# VIM2-AccelController.net
KiCad netlist of a schematic drawn in EAGLE
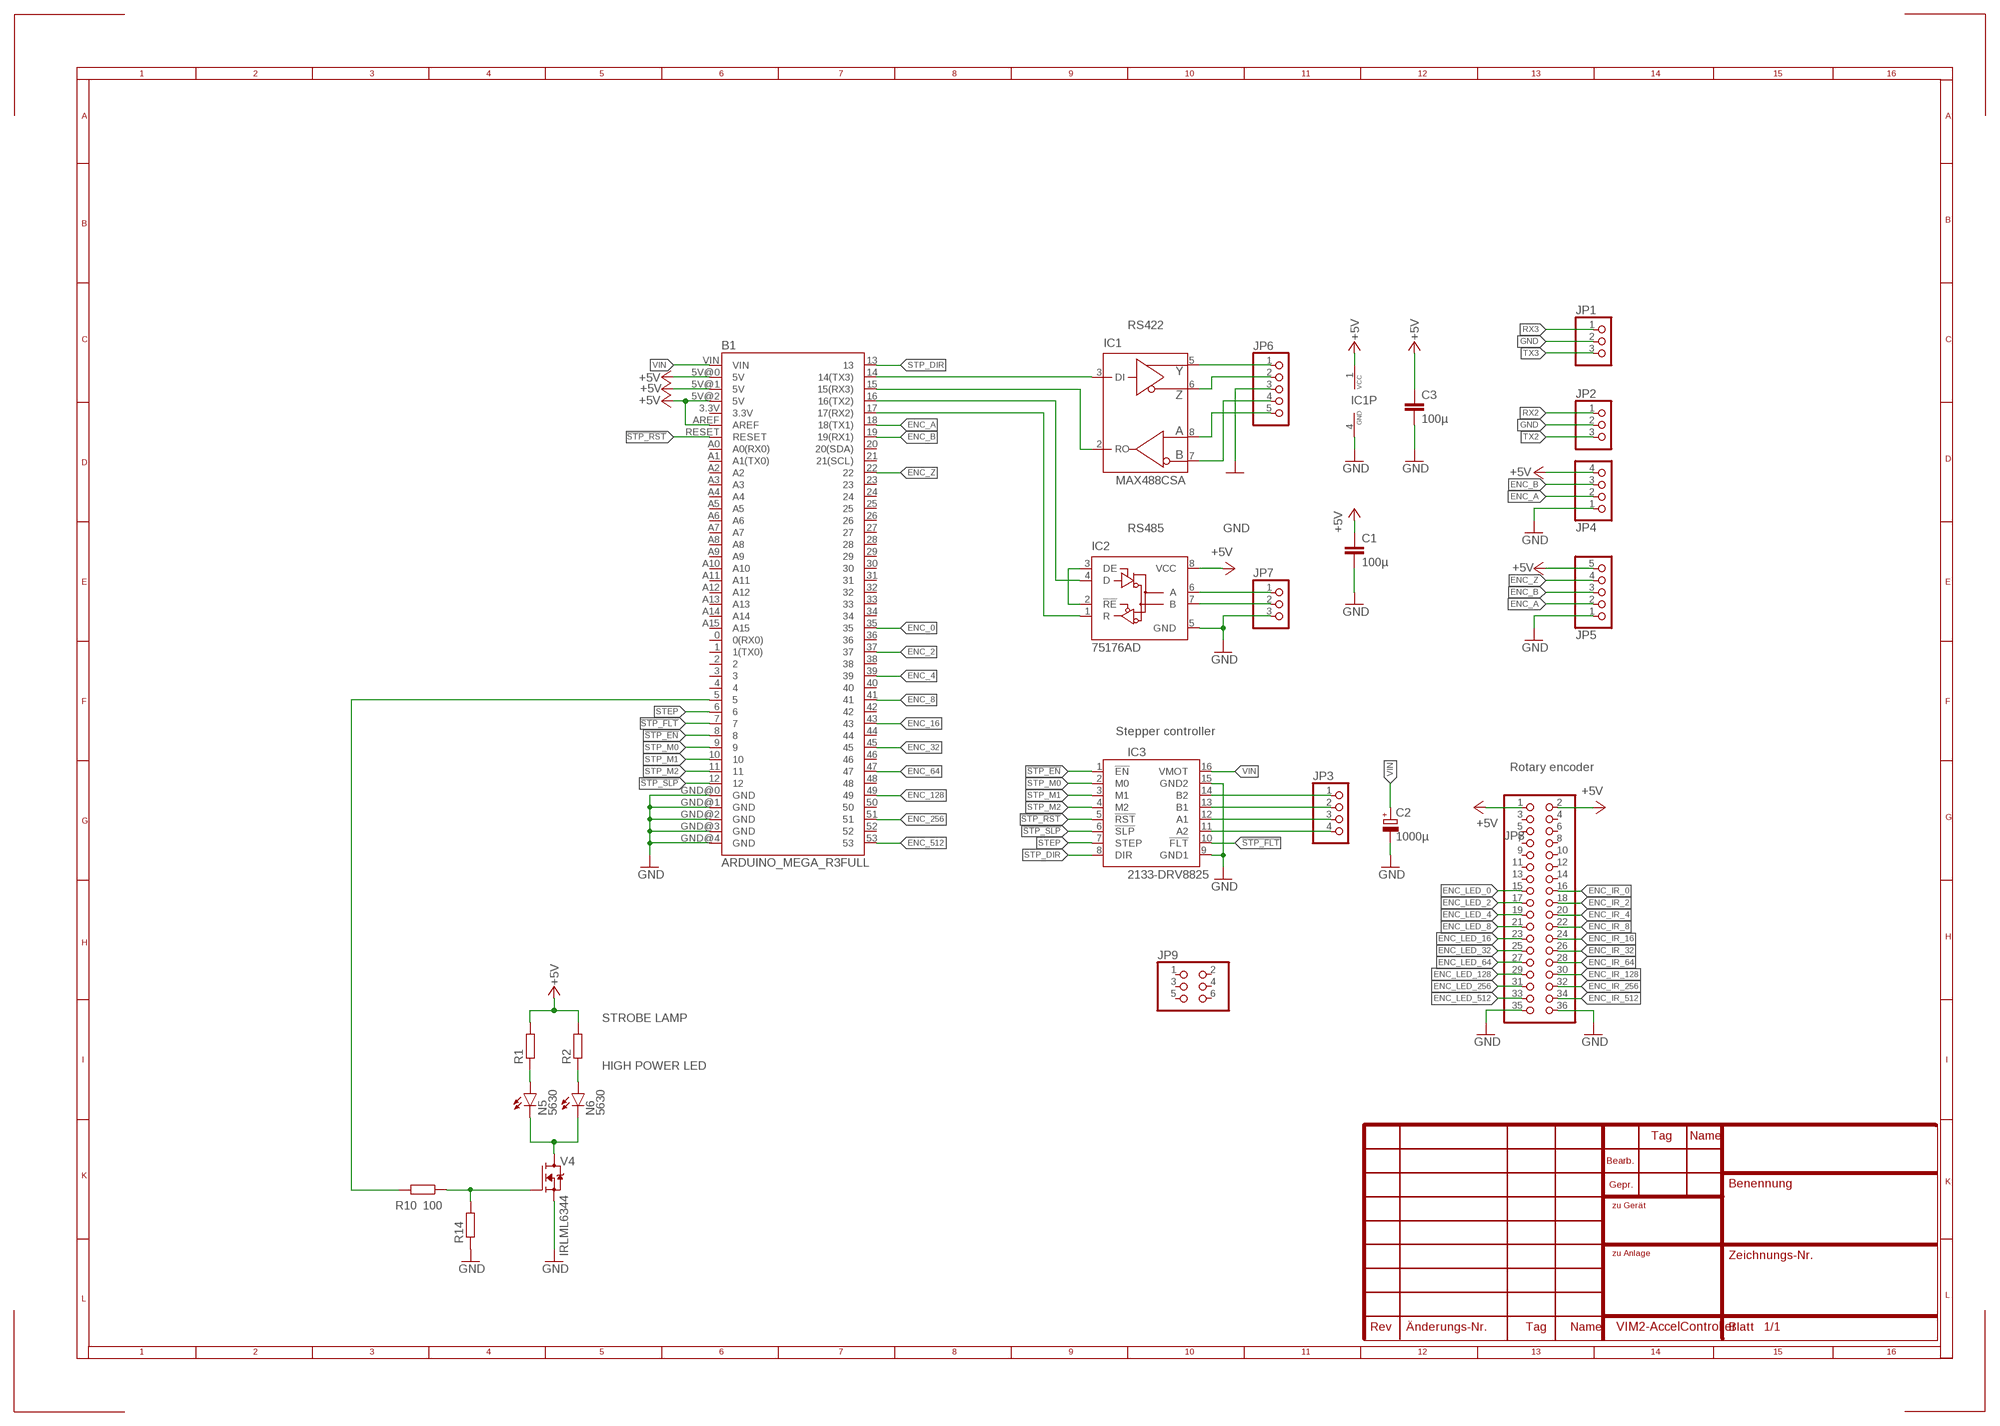
[diagram p0: schematic, sheet 1]

(export (version "E")
  (design (tool "Eeschema 10.0.6"))
  (components
    (comp (ref "B1")
      (value "ARDUINO_MEGA_R3FULL")
      (footprint "eagle-import:ARDUINO_MEGA")
      (libsource (lib "eagle-import") (part "ARDUINO_MEGA_R3FULL"))
    )
    (comp (ref "C1")
      (value "100µ")
      (footprint "eagle-import:C0805K")
      (libsource (lib "eagle-import") (part "C-EUC0805K"))
    )
    (comp (ref "C2")
      (value "1000µ")
      (footprint "eagle-import:E5-8,5")
      (libsource (lib "eagle-import") (part "CPOL-EUE5-8.5"))
    )
    (comp (ref "C3")
      (value "100µ")
      (footprint "eagle-import:C0805K")
      (libsource (lib "eagle-import") (part "C-EUC0805K"))
    )
    (comp (ref "IC1")
      (value "MAX488CSA")
      (footprint "eagle-import:SO08")
      (fields (field (name "MF") "MAXIM"))
      (libsource (lib "eagle-import") (part "MAX488CSA"))
    )
    (comp (ref "IC2")
      (value "75176AD")
      (footprint "eagle-import:D_R-PDSO-G8")
      (libsource (lib "eagle-import") (part "75176AD"))
    )
    (comp (ref "IC3")
      (value "2133-DRV8825")
      (footprint "eagle-import:DRV8825")
      (libsource (lib "eagle-import") (part "2133-DRV8825"))
    )
    (comp (ref "JP1")
      (value "PINHD-1X3")
      (footprint "eagle-import:1X03")
      (libsource (lib "eagle-import") (part "PINHD-1X3"))
    )
    (comp (ref "JP2")
      (value "PINHD-1X3")
      (footprint "eagle-import:1X03")
      (libsource (lib "eagle-import") (part "PINHD-1X3"))
    )
    (comp (ref "JP3")
      (value "PINHD-1X4/90")
      (footprint "eagle-import:1X04_90")
      (libsource (lib "eagle-import") (part "PINHD-1X4/90"))
    )
    (comp (ref "JP4")
      (value "PINHD-1X4")
      (footprint "eagle-import:1X04")
      (libsource (lib "eagle-import") (part "PINHD-1X4"))
    )
    (comp (ref "JP5")
      (value "PINHD-1X5")
      (footprint "eagle-import:1X05")
      (libsource (lib "eagle-import") (part "PINHD-1X5"))
    )
    (comp (ref "JP6")
      (value "PINHD-1X5")
      (footprint "eagle-import:1X05")
      (libsource (lib "eagle-import") (part "PINHD-1X5"))
    )
    (comp (ref "JP7")
      (value "PINHD-1X3")
      (footprint "eagle-import:1X03")
      (libsource (lib "eagle-import") (part "PINHD-1X3"))
    )
    (comp (ref "JP8")
      (value "PINHD-2X18")
      (footprint "eagle-import:2X18")
      (libsource (lib "eagle-import") (part "PINHD-2X18"))
    )
    (comp (ref "JP9")
      (value "PINHD-2X3")
      (footprint "eagle-import:2X03")
      (libsource (lib "eagle-import") (part "PINHD-2X3"))
    )
    (comp (ref "N5")
      (value "5630")
      (footprint "eagle-import:5730")
      (libsource (lib "eagle-import") (part "5630"))
    )
    (comp (ref "N6")
      (value "5630")
      (footprint "eagle-import:5730")
      (libsource (lib "eagle-import") (part "5630"))
    )
    (comp (ref "R1")
      (value "100")
      (footprint "eagle-import:R0805")
      (libsource (lib "eagle-import") (part "R-EU_R0805"))
    )
    (comp (ref "R2")
      (value "100")
      (footprint "eagle-import:R0805")
      (libsource (lib "eagle-import") (part "R-EU_R0805"))
    )
    (comp (ref "R10")
      (value "100")
      (footprint "eagle-import:R0805")
      (libsource (lib "eagle-import") (part "R-EU_R0805"))
    )
    (comp (ref "R14")
      (value "4k7")
      (footprint "eagle-import:R0805")
      (libsource (lib "eagle-import") (part "R-EU_R0805"))
    )
    (comp (ref "V4")
      (value "IRLML6344")
      (footprint "eagle-import:SOT23")
      (libsource (lib "eagle-import") (part "IRLML6344"))
    )
  )
  (nets
    (net (code "1") (name "+5V") (class "Default")
      (node (ref "B1") (pin "5V@0") (pinfunction "5V_5V@0") (pintype "bidirectional"))
      (node (ref "B1") (pin "5V@1") (pinfunction "5V_5V@1") (pintype "bidirectional"))
      (node (ref "B1") (pin "5V@2") (pinfunction "5V_5V@2") (pintype "bidirectional"))
      (node (ref "B1") (pin "AREF") (pinfunction "AREF_AREF") (pintype "bidirectional"))
      (node (ref "C1") (pin "1") (pinfunction "1_1") (pintype "passive"))
      (node (ref "C3") (pin "1") (pinfunction "1_1") (pintype "passive"))
      (node (ref "IC1") (pin "1") (pinfunction "VCC_1") (pintype "power_in"))
      (node (ref "IC2") (pin "8") (pinfunction "VCC_8") (pintype "power_in"))
      (node (ref "JP4") (pin "4") (pinfunction "4_4") (pintype "passive"))
      (node (ref "JP5") (pin "5") (pinfunction "5_5") (pintype "passive"))
      (node (ref "JP8") (pin "1") (pinfunction "1_1") (pintype "passive"))
      (node (ref "JP8") (pin "2") (pinfunction "2_2") (pintype "passive"))
      (node (ref "R1") (pin "2") (pinfunction "2_2") (pintype "passive"))
      (node (ref "R2") (pin "2") (pinfunction "2_2") (pintype "passive"))
    )
    (net (code "2") (name "/~{STP_EN}") (class "Default")
      (node (ref "B1") (pin "8") (pinfunction "8_8") (pintype "bidirectional"))
      (node (ref "IC3") (pin "1") (pinfunction "~{EN}_1") (pintype "passive"))
    )
    (net (code "3") (name "/~{STP_FLT}") (class "Default")
      (node (ref "B1") (pin "7") (pinfunction "7_7") (pintype "bidirectional"))
      (node (ref "IC3") (pin "10") (pinfunction "~{FLT}_10") (pintype "open_collector"))
    )
    (net (code "4") (name "/~{STP_RST}") (class "Default")
      (node (ref "B1") (pin "RESET") (pinfunction "RESET_RESET") (pintype "bidirectional"))
      (node (ref "IC3") (pin "5") (pinfunction "~{RST}_5") (pintype "input"))
    )
    (net (code "5") (name "/~{STP_SLP}") (class "Default")
      (node (ref "B1") (pin "12") (pinfunction "12_12") (pintype "bidirectional"))
      (node (ref "IC3") (pin "6") (pinfunction "~{SLP}_6") (pintype "input"))
    )
    (net (code "6") (name "ENC_0") (class "Default")
      (node (ref "B1") (pin "35") (pinfunction "35_35") (pintype "bidirectional"))
    )
    (net (code "7") (name "ENC_2") (class "Default")
      (node (ref "B1") (pin "37") (pinfunction "37_37") (pintype "bidirectional"))
    )
    (net (code "8") (name "ENC_4") (class "Default")
      (node (ref "B1") (pin "39") (pinfunction "39_39") (pintype "bidirectional"))
    )
    (net (code "9") (name "ENC_8") (class "Default")
      (node (ref "B1") (pin "41") (pinfunction "41_41") (pintype "bidirectional"))
    )
    (net (code "10") (name "ENC_16") (class "Default")
      (node (ref "B1") (pin "43") (pinfunction "43_43") (pintype "bidirectional"))
    )
    (net (code "11") (name "ENC_32") (class "Default")
      (node (ref "B1") (pin "45") (pinfunction "45_45") (pintype "bidirectional"))
    )
    (net (code "12") (name "ENC_64") (class "Default")
      (node (ref "B1") (pin "47") (pinfunction "47_47") (pintype "bidirectional"))
    )
    (net (code "13") (name "ENC_128") (class "Default")
      (node (ref "B1") (pin "49") (pinfunction "49_49") (pintype "bidirectional"))
    )
    (net (code "14") (name "ENC_256") (class "Default")
      (node (ref "B1") (pin "51") (pinfunction "51_51") (pintype "bidirectional"))
    )
    (net (code "15") (name "ENC_512") (class "Default")
      (node (ref "B1") (pin "53") (pinfunction "53_53") (pintype "bidirectional"))
    )
    (net (code "16") (name "ENC_A") (class "Default")
      (node (ref "B1") (pin "18") (pinfunction "18(TX1)_18") (pintype "bidirectional"))
      (node (ref "JP4") (pin "2") (pinfunction "2_2") (pintype "passive"))
      (node (ref "JP5") (pin "2") (pinfunction "2_2") (pintype "passive"))
    )
    (net (code "17") (name "ENC_B") (class "Default")
      (node (ref "B1") (pin "19") (pinfunction "19(RX1)_19") (pintype "bidirectional"))
      (node (ref "JP4") (pin "3") (pinfunction "3_3") (pintype "passive"))
      (node (ref "JP5") (pin "3") (pinfunction "3_3") (pintype "passive"))
    )
    (net (code "18") (name "ENC_IR_0") (class "Default")
      (node (ref "JP8") (pin "16") (pinfunction "16_16") (pintype "passive"))
    )
    (net (code "19") (name "ENC_IR_2") (class "Default")
      (node (ref "JP8") (pin "18") (pinfunction "18_18") (pintype "passive"))
    )
    (net (code "20") (name "ENC_IR_4") (class "Default")
      (node (ref "JP8") (pin "20") (pinfunction "20_20") (pintype "passive"))
    )
    (net (code "21") (name "ENC_IR_8") (class "Default")
      (node (ref "JP8") (pin "22") (pinfunction "22_22") (pintype "passive"))
    )
    (net (code "22") (name "ENC_IR_16") (class "Default")
      (node (ref "JP8") (pin "24") (pinfunction "24_24") (pintype "passive"))
    )
    (net (code "23") (name "ENC_IR_32") (class "Default")
      (node (ref "JP8") (pin "26") (pinfunction "26_26") (pintype "passive"))
    )
    (net (code "24") (name "ENC_IR_64") (class "Default")
      (node (ref "JP8") (pin "28") (pinfunction "28_28") (pintype "passive"))
    )
    (net (code "25") (name "ENC_IR_128") (class "Default")
      (node (ref "JP8") (pin "30") (pinfunction "30_30") (pintype "passive"))
    )
    (net (code "26") (name "ENC_IR_256") (class "Default")
      (node (ref "JP8") (pin "32") (pinfunction "32_32") (pintype "passive"))
    )
    (net (code "27") (name "ENC_IR_512") (class "Default")
      (node (ref "JP8") (pin "34") (pinfunction "34_34") (pintype "passive"))
    )
    (net (code "28") (name "ENC_LED_0") (class "Default")
      (node (ref "JP8") (pin "15") (pinfunction "15_15") (pintype "passive"))
    )
    (net (code "29") (name "ENC_LED_2") (class "Default")
      (node (ref "JP8") (pin "17") (pinfunction "17_17") (pintype "passive"))
    )
    (net (code "30") (name "ENC_LED_4") (class "Default")
      (node (ref "JP8") (pin "19") (pinfunction "19_19") (pintype "passive"))
    )
    (net (code "31") (name "ENC_LED_8") (class "Default")
      (node (ref "JP8") (pin "21") (pinfunction "21_21") (pintype "passive"))
    )
    (net (code "32") (name "ENC_LED_16") (class "Default")
      (node (ref "JP8") (pin "23") (pinfunction "23_23") (pintype "passive"))
    )
    (net (code "33") (name "ENC_LED_32") (class "Default")
      (node (ref "JP8") (pin "25") (pinfunction "25_25") (pintype "passive"))
    )
    (net (code "34") (name "ENC_LED_64") (class "Default")
      (node (ref "JP8") (pin "27") (pinfunction "27_27") (pintype "passive"))
    )
    (net (code "35") (name "ENC_LED_128") (class "Default")
      (node (ref "JP8") (pin "29") (pinfunction "29_29") (pintype "passive"))
    )
    (net (code "36") (name "ENC_LED_256") (class "Default")
      (node (ref "JP8") (pin "31") (pinfunction "31_31") (pintype "passive"))
    )
    (net (code "37") (name "ENC_LED_512") (class "Default")
      (node (ref "JP8") (pin "33") (pinfunction "33_33") (pintype "passive"))
    )
    (net (code "38") (name "ENC_Z") (class "Default")
      (node (ref "B1") (pin "22") (pinfunction "22_22") (pintype "bidirectional"))
      (node (ref "JP5") (pin "4") (pinfunction "4_4") (pintype "passive"))
    )
    (net (code "39") (name "GND") (class "Default")
      (node (ref "B1") (pin "GND@0") (pinfunction "GND_GND@0") (pintype "bidirectional"))
      (node (ref "B1") (pin "GND@1") (pinfunction "GND_GND@1") (pintype "bidirectional"))
      (node (ref "B1") (pin "GND@2") (pinfunction "GND_GND@2") (pintype "bidirectional"))
      (node (ref "B1") (pin "GND@3") (pinfunction "GND_GND@3") (pintype "bidirectional"))
      (node (ref "B1") (pin "GND@4") (pinfunction "GND_GND@4") (pintype "bidirectional"))
      (node (ref "C1") (pin "2") (pinfunction "2_2") (pintype "passive"))
      (node (ref "C2") (pin "-") (pinfunction "-_-") (pintype "passive"))
      (node (ref "C3") (pin "2") (pinfunction "2_2") (pintype "passive"))
      (node (ref "IC1") (pin "4") (pinfunction "GND_4") (pintype "power_in"))
      (node (ref "IC2") (pin "5") (pinfunction "GND_5") (pintype "power_in"))
      (node (ref "IC3") (pin "15") (pinfunction "GND2_15") (pintype "power_in"))
      (node (ref "IC3") (pin "9") (pinfunction "GND1_9") (pintype "power_in"))
      (node (ref "JP1") (pin "2") (pinfunction "2_2") (pintype "passive"))
      (node (ref "JP2") (pin "2") (pinfunction "2_2") (pintype "passive"))
      (node (ref "JP4") (pin "1") (pinfunction "1_1") (pintype "passive"))
      (node (ref "JP5") (pin "1") (pinfunction "1_1") (pintype "passive"))
      (node (ref "JP6") (pin "3") (pinfunction "3_3") (pintype "passive"))
      (node (ref "JP7") (pin "3") (pinfunction "3_3") (pintype "passive"))
      (node (ref "JP8") (pin "35") (pinfunction "35_35") (pintype "passive"))
      (node (ref "JP8") (pin "36") (pinfunction "36_36") (pintype "passive"))
      (node (ref "R14") (pin "1") (pinfunction "1_1") (pintype "passive"))
      (node (ref "V4") (pin "2") (pinfunction "S_2") (pintype "passive"))
    )
    (net (code "40") (name "Net-(B1-Pad5)") (class "Default")
      (node (ref "B1") (pin "5") (pinfunction "5_5") (pintype "bidirectional"))
      (node (ref "R10") (pin "2") (pinfunction "2_2") (pintype "passive"))
    )
    (net (code "41") (name "Net-(IC1A-A)") (class "Default")
      (node (ref "IC1") (pin "8") (pinfunction "A_8") (pintype "input"))
      (node (ref "JP6") (pin "5") (pinfunction "5_5") (pintype "passive"))
    )
    (net (code "42") (name "Net-(IC1A-B)") (class "Default")
      (node (ref "IC1") (pin "7") (pinfunction "B_7") (pintype "input"))
      (node (ref "JP6") (pin "4") (pinfunction "4_4") (pintype "passive"))
    )
    (net (code "43") (name "Net-(IC1A-Y)") (class "Default")
      (node (ref "IC1") (pin "5") (pinfunction "Y_5") (pintype "output"))
      (node (ref "JP6") (pin "1") (pinfunction "1_1") (pintype "passive"))
    )
    (net (code "44") (name "Net-(IC1A-Z)") (class "Default")
      (node (ref "IC1") (pin "6") (pinfunction "Z_6") (pintype "output"))
      (node (ref "JP6") (pin "2") (pinfunction "2_2") (pintype "passive"))
    )
    (net (code "45") (name "Net-(IC2-A)") (class "Default")
      (node (ref "IC2") (pin "6") (pinfunction "A_6") (pintype "output"))
      (node (ref "JP7") (pin "1") (pinfunction "1_1") (pintype "passive"))
    )
    (net (code "46") (name "Net-(IC2-B)") (class "Default")
      (node (ref "IC2") (pin "7") (pinfunction "B_7") (pintype "output"))
      (node (ref "JP7") (pin "2") (pinfunction "2_2") (pintype "passive"))
    )
    (net (code "47") (name "Net-(IC2-DE)") (class "Default")
      (node (ref "IC2") (pin "2") (pinfunction "~{RE}_2") (pintype "input"))
      (node (ref "IC2") (pin "3") (pinfunction "DE_3") (pintype "input"))
    )
    (net (code "48") (name "Net-(IC3-A1)") (class "Default")
      (node (ref "IC3") (pin "12") (pinfunction "A1_12") (pintype "output"))
      (node (ref "JP3") (pin "3") (pinfunction "3_3") (pintype "passive"))
    )
    (net (code "49") (name "Net-(IC3-A2)") (class "Default")
      (node (ref "IC3") (pin "11") (pinfunction "A2_11") (pintype "output"))
      (node (ref "JP3") (pin "4") (pinfunction "4_4") (pintype "passive"))
    )
    (net (code "50") (name "Net-(IC3-B1)") (class "Default")
      (node (ref "IC3") (pin "13") (pinfunction "B1_13") (pintype "output"))
      (node (ref "JP3") (pin "2") (pinfunction "2_2") (pintype "passive"))
    )
    (net (code "51") (name "Net-(IC3-B2)") (class "Default")
      (node (ref "IC3") (pin "14") (pinfunction "B2_14") (pintype "output"))
      (node (ref "JP3") (pin "1") (pinfunction "1_1") (pintype "passive"))
    )
    (net (code "52") (name "Net-(N5-A-PadP$1)") (class "Default")
      (node (ref "N5") (pin "P$1") (pinfunction "A_P$1") (pintype "passive"))
      (node (ref "N5") (pin "P$2") (pinfunction "A_P$2") (pintype "passive"))
      (node (ref "R1") (pin "1") (pinfunction "1_1") (pintype "passive"))
    )
    (net (code "53") (name "Net-(N5-C)") (class "Default")
      (node (ref "N5") (pin "P$3") (pinfunction "C_P$3") (pintype "passive"))
      (node (ref "N6") (pin "P$3") (pinfunction "C_P$3") (pintype "passive"))
      (node (ref "V4") (pin "3") (pinfunction "D_3") (pintype "passive"))
    )
    (net (code "54") (name "Net-(N6-A-PadP$1)") (class "Default")
      (node (ref "N6") (pin "P$1") (pinfunction "A_P$1") (pintype "passive"))
      (node (ref "N6") (pin "P$2") (pinfunction "A_P$2") (pintype "passive"))
      (node (ref "R2") (pin "1") (pinfunction "1_1") (pintype "passive"))
    )
    (net (code "55") (name "Net-(V4-G)") (class "Default")
      (node (ref "R10") (pin "1") (pinfunction "1_1") (pintype "passive"))
      (node (ref "R14") (pin "2") (pinfunction "2_2") (pintype "passive"))
      (node (ref "V4") (pin "1") (pinfunction "G_1") (pintype "passive"))
    )
    (net (code "56") (name "RX2") (class "Default")
      (node (ref "B1") (pin "17") (pinfunction "17(RX2)_17") (pintype "bidirectional"))
      (node (ref "IC2") (pin "1") (pinfunction "R_1") (pintype "input"))
      (node (ref "JP2") (pin "1") (pinfunction "1_1") (pintype "passive"))
    )
    (net (code "57") (name "RX3") (class "Default")
      (node (ref "B1") (pin "15") (pinfunction "15(RX3)_15") (pintype "bidirectional"))
      (node (ref "IC1") (pin "2") (pinfunction "RO_2") (pintype "output"))
      (node (ref "JP1") (pin "1") (pinfunction "1_1") (pintype "passive"))
    )
    (net (code "58") (name "STEP") (class "Default")
      (node (ref "B1") (pin "6") (pinfunction "6_6") (pintype "bidirectional"))
      (node (ref "IC3") (pin "7") (pinfunction "STEP_7") (pintype "input"))
    )
    (net (code "59") (name "STP_DIR") (class "Default")
      (node (ref "B1") (pin "13") (pinfunction "13_13") (pintype "bidirectional"))
      (node (ref "IC3") (pin "8") (pinfunction "DIR_8") (pintype "input"))
    )
    (net (code "60") (name "STP_M0") (class "Default")
      (node (ref "B1") (pin "9") (pinfunction "9_9") (pintype "bidirectional"))
      (node (ref "IC3") (pin "2") (pinfunction "M0_2") (pintype "passive"))
    )
    (net (code "61") (name "STP_M1") (class "Default")
      (node (ref "B1") (pin "10") (pinfunction "10_10") (pintype "bidirectional"))
      (node (ref "IC3") (pin "3") (pinfunction "M1_3") (pintype "passive"))
    )
    (net (code "62") (name "STP_M2") (class "Default")
      (node (ref "B1") (pin "11") (pinfunction "11_11") (pintype "bidirectional"))
      (node (ref "IC3") (pin "4") (pinfunction "M2_4") (pintype "passive"))
    )
    (net (code "63") (name "TX2") (class "Default")
      (node (ref "B1") (pin "16") (pinfunction "16(TX2)_16") (pintype "bidirectional"))
      (node (ref "IC2") (pin "4") (pinfunction "D_4") (pintype "input"))
      (node (ref "JP2") (pin "3") (pinfunction "3_3") (pintype "passive"))
    )
    (net (code "64") (name "TX3") (class "Default")
      (node (ref "B1") (pin "14") (pinfunction "14(TX3)_14") (pintype "bidirectional"))
      (node (ref "IC1") (pin "3") (pinfunction "DI_3") (pintype "input"))
      (node (ref "JP1") (pin "3") (pinfunction "3_3") (pintype "passive"))
    )
    (net (code "65") (name "VIN") (class "Default")
      (node (ref "B1") (pin "VIN") (pinfunction "VIN_VIN") (pintype "bidirectional"))
      (node (ref "C2") (pin "+") (pinfunction "+_+") (pintype "passive"))
      (node (ref "IC3") (pin "16") (pinfunction "VMOT_16") (pintype "power_in"))
    )
    (net (code "66") (name "unconnected-(B1-0(RX0)-Pad0)") (class "Default")
      (node (ref "B1") (pin "0") (pinfunction "0(RX0)_0") (pintype "bidirectional"))
    )
    (net (code "67") (name "unconnected-(B1-1(TX0)-Pad1)") (class "Default")
      (node (ref "B1") (pin "1") (pinfunction "1(TX0)_1") (pintype "bidirectional"))
    )
    (net (code "68") (name "unconnected-(B1-20(SDA)-Pad20)") (class "Default")
      (node (ref "B1") (pin "20") (pinfunction "20(SDA)_20") (pintype "bidirectional"))
    )
    (net (code "69") (name "unconnected-(B1-21(SCL)-Pad21)") (class "Default")
      (node (ref "B1") (pin "21") (pinfunction "21(SCL)_21") (pintype "bidirectional"))
    )
    (net (code "70") (name "unconnected-(B1-A0(RX0)-PadA0)") (class "Default")
      (node (ref "B1") (pin "A0") (pinfunction "A0(RX0)_A0") (pintype "bidirectional"))
    )
    (net (code "71") (name "unconnected-(B1-A1(TX0)-PadA1)") (class "Default")
      (node (ref "B1") (pin "A1") (pinfunction "A1(TX0)_A1") (pintype "bidirectional"))
    )
    (net (code "72") (name "unconnected-(B1-Pad2)") (class "Default")
      (node (ref "B1") (pin "2") (pinfunction "2_2") (pintype "bidirectional"))
    )
    (net (code "73") (name "unconnected-(B1-Pad3)") (class "Default")
      (node (ref "B1") (pin "3") (pinfunction "3_3") (pintype "bidirectional"))
    )
    (net (code "74") (name "unconnected-(B1-Pad3.3V)") (class "Default")
      (node (ref "B1") (pin "3.3V") (pinfunction "3.3V_3.3V") (pintype "bidirectional"))
    )
    (net (code "75") (name "unconnected-(B1-Pad4)") (class "Default")
      (node (ref "B1") (pin "4") (pinfunction "4_4") (pintype "bidirectional"))
    )
    (net (code "76") (name "unconnected-(B1-Pad23)") (class "Default")
      (node (ref "B1") (pin "23") (pinfunction "23_23") (pintype "bidirectional"))
    )
    (net (code "77") (name "unconnected-(B1-Pad24)") (class "Default")
      (node (ref "B1") (pin "24") (pinfunction "24_24") (pintype "bidirectional"))
    )
    (net (code "78") (name "unconnected-(B1-Pad25)") (class "Default")
      (node (ref "B1") (pin "25") (pinfunction "25_25") (pintype "bidirectional"))
    )
    (net (code "79") (name "unconnected-(B1-Pad26)") (class "Default")
      (node (ref "B1") (pin "26") (pinfunction "26_26") (pintype "bidirectional"))
    )
    (net (code "80") (name "unconnected-(B1-Pad27)") (class "Default")
      (node (ref "B1") (pin "27") (pinfunction "27_27") (pintype "bidirectional"))
    )
    (net (code "81") (name "unconnected-(B1-Pad28)") (class "Default")
      (node (ref "B1") (pin "28") (pinfunction "28_28") (pintype "bidirectional"))
    )
    (net (code "82") (name "unconnected-(B1-Pad29)") (class "Default")
      (node (ref "B1") (pin "29") (pinfunction "29_29") (pintype "bidirectional"))
    )
    (net (code "83") (name "unconnected-(B1-Pad30)") (class "Default")
      (node (ref "B1") (pin "30") (pinfunction "30_30") (pintype "bidirectional"))
    )
    (net (code "84") (name "unconnected-(B1-Pad31)") (class "Default")
      (node (ref "B1") (pin "31") (pinfunction "31_31") (pintype "bidirectional"))
    )
    (net (code "85") (name "unconnected-(B1-Pad32)") (class "Default")
      (node (ref "B1") (pin "32") (pinfunction "32_32") (pintype "bidirectional"))
    )
    (net (code "86") (name "unconnected-(B1-Pad33)") (class "Default")
      (node (ref "B1") (pin "33") (pinfunction "33_33") (pintype "bidirectional"))
    )
    (net (code "87") (name "unconnected-(B1-Pad34)") (class "Default")
      (node (ref "B1") (pin "34") (pinfunction "34_34") (pintype "bidirectional"))
    )
    (net (code "88") (name "unconnected-(B1-Pad36)") (class "Default")
      (node (ref "B1") (pin "36") (pinfunction "36_36") (pintype "bidirectional"))
    )
    (net (code "89") (name "unconnected-(B1-Pad38)") (class "Default")
      (node (ref "B1") (pin "38") (pinfunction "38_38") (pintype "bidirectional"))
    )
    (net (code "90") (name "unconnected-(B1-Pad40)") (class "Default")
      (node (ref "B1") (pin "40") (pinfunction "40_40") (pintype "bidirectional"))
    )
    (net (code "91") (name "unconnected-(B1-Pad42)") (class "Default")
      (node (ref "B1") (pin "42") (pinfunction "42_42") (pintype "bidirectional"))
    )
    (net (code "92") (name "unconnected-(B1-Pad44)") (class "Default")
      (node (ref "B1") (pin "44") (pinfunction "44_44") (pintype "bidirectional"))
    )
    (net (code "93") (name "unconnected-(B1-Pad46)") (class "Default")
      (node (ref "B1") (pin "46") (pinfunction "46_46") (pintype "bidirectional"))
    )
    (net (code "94") (name "unconnected-(B1-Pad48)") (class "Default")
      (node (ref "B1") (pin "48") (pinfunction "48_48") (pintype "bidirectional"))
    )
    (net (code "95") (name "unconnected-(B1-Pad50)") (class "Default")
      (node (ref "B1") (pin "50") (pinfunction "50_50") (pintype "bidirectional"))
    )
    (net (code "96") (name "unconnected-(B1-Pad52)") (class "Default")
      (node (ref "B1") (pin "52") (pinfunction "52_52") (pintype "bidirectional"))
    )
    (net (code "97") (name "unconnected-(B1-PadA2)") (class "Default")
      (node (ref "B1") (pin "A2") (pinfunction "A2_A2") (pintype "bidirectional"))
    )
    (net (code "98") (name "unconnected-(B1-PadA3)") (class "Default")
      (node (ref "B1") (pin "A3") (pinfunction "A3_A3") (pintype "bidirectional"))
    )
    (net (code "99") (name "unconnected-(B1-PadA4)") (class "Default")
      (node (ref "B1") (pin "A4") (pinfunction "A4_A4") (pintype "bidirectional"))
    )
    (net (code "100") (name "unconnected-(B1-PadA5)") (class "Default")
      (node (ref "B1") (pin "A5") (pinfunction "A5_A5") (pintype "bidirectional"))
    )
    (net (code "101") (name "unconnected-(B1-PadA6)") (class "Default")
      (node (ref "B1") (pin "A6") (pinfunction "A6_A6") (pintype "bidirectional"))
    )
    (net (code "102") (name "unconnected-(B1-PadA7)") (class "Default")
      (node (ref "B1") (pin "A7") (pinfunction "A7_A7") (pintype "bidirectional"))
    )
    (net (code "103") (name "unconnected-(B1-PadA8)") (class "Default")
      (node (ref "B1") (pin "A8") (pinfunction "A8_A8") (pintype "bidirectional"))
    )
    (net (code "104") (name "unconnected-(B1-PadA9)") (class "Default")
      (node (ref "B1") (pin "A9") (pinfunction "A9_A9") (pintype "bidirectional"))
    )
    (net (code "105") (name "unconnected-(B1-PadA10)") (class "Default")
      (node (ref "B1") (pin "A10") (pinfunction "A10_A10") (pintype "bidirectional"))
    )
    (net (code "106") (name "unconnected-(B1-PadA11)") (class "Default")
      (node (ref "B1") (pin "A11") (pinfunction "A11_A11") (pintype "bidirectional"))
    )
    (net (code "107") (name "unconnected-(B1-PadA12)") (class "Default")
      (node (ref "B1") (pin "A12") (pinfunction "A12_A12") (pintype "bidirectional"))
    )
    (net (code "108") (name "unconnected-(B1-PadA13)") (class "Default")
      (node (ref "B1") (pin "A13") (pinfunction "A13_A13") (pintype "bidirectional"))
    )
    (net (code "109") (name "unconnected-(B1-PadA14)") (class "Default")
      (node (ref "B1") (pin "A14") (pinfunction "A14_A14") (pintype "bidirectional"))
    )
    (net (code "110") (name "unconnected-(B1-PadA15)") (class "Default")
      (node (ref "B1") (pin "A15") (pinfunction "A15_A15") (pintype "bidirectional"))
    )
    (net (code "111") (name "unconnected-(JP8-Pad3)") (class "Default")
      (node (ref "JP8") (pin "3") (pinfunction "3_3") (pintype "passive"))
    )
    (net (code "112") (name "unconnected-(JP8-Pad4)") (class "Default")
      (node (ref "JP8") (pin "4") (pinfunction "4_4") (pintype "passive"))
    )
    (net (code "113") (name "unconnected-(JP8-Pad5)") (class "Default")
      (node (ref "JP8") (pin "5") (pinfunction "5_5") (pintype "passive"))
    )
    (net (code "114") (name "unconnected-(JP8-Pad6)") (class "Default")
      (node (ref "JP8") (pin "6") (pinfunction "6_6") (pintype "passive"))
    )
    (net (code "115") (name "unconnected-(JP8-Pad7)") (class "Default")
      (node (ref "JP8") (pin "7") (pinfunction "7_7") (pintype "passive"))
    )
    (net (code "116") (name "unconnected-(JP8-Pad8)") (class "Default")
      (node (ref "JP8") (pin "8") (pinfunction "8_8") (pintype "passive"))
    )
    (net (code "117") (name "unconnected-(JP8-Pad9)") (class "Default")
      (node (ref "JP8") (pin "9") (pinfunction "9_9") (pintype "passive"))
    )
    (net (code "118") (name "unconnected-(JP8-Pad10)") (class "Default")
      (node (ref "JP8") (pin "10") (pinfunction "10_10") (pintype "passive"))
    )
    (net (code "119") (name "unconnected-(JP8-Pad11)") (class "Default")
      (node (ref "JP8") (pin "11") (pinfunction "11_11") (pintype "passive"))
    )
    (net (code "120") (name "unconnected-(JP8-Pad12)") (class "Default")
      (node (ref "JP8") (pin "12") (pinfunction "12_12") (pintype "passive"))
    )
    (net (code "121") (name "unconnected-(JP8-Pad13)") (class "Default")
      (node (ref "JP8") (pin "13") (pinfunction "13_13") (pintype "passive"))
    )
    (net (code "122") (name "unconnected-(JP8-Pad14)") (class "Default")
      (node (ref "JP8") (pin "14") (pinfunction "14_14") (pintype "passive"))
    )
    (net (code "123") (name "unconnected-(JP9-Pad1)") (class "Default")
      (node (ref "JP9") (pin "1") (pinfunction "1_1") (pintype "passive"))
    )
    (net (code "124") (name "unconnected-(JP9-Pad2)") (class "Default")
      (node (ref "JP9") (pin "2") (pinfunction "2_2") (pintype "passive"))
    )
    (net (code "125") (name "unconnected-(JP9-Pad3)") (class "Default")
      (node (ref "JP9") (pin "3") (pinfunction "3_3") (pintype "passive"))
    )
    (net (code "126") (name "unconnected-(JP9-Pad4)") (class "Default")
      (node (ref "JP9") (pin "4") (pinfunction "4_4") (pintype "passive"))
    )
    (net (code "127") (name "unconnected-(JP9-Pad5)") (class "Default")
      (node (ref "JP9") (pin "5") (pinfunction "5_5") (pintype "passive"))
    )
    (net (code "128") (name "unconnected-(JP9-Pad6)") (class "Default")
      (node (ref "JP9") (pin "6") (pinfunction "6_6") (pintype "passive"))
    )
  )
)
